# relay_sch.net
KiCad netlist of a schematic drawn in Altium Designer
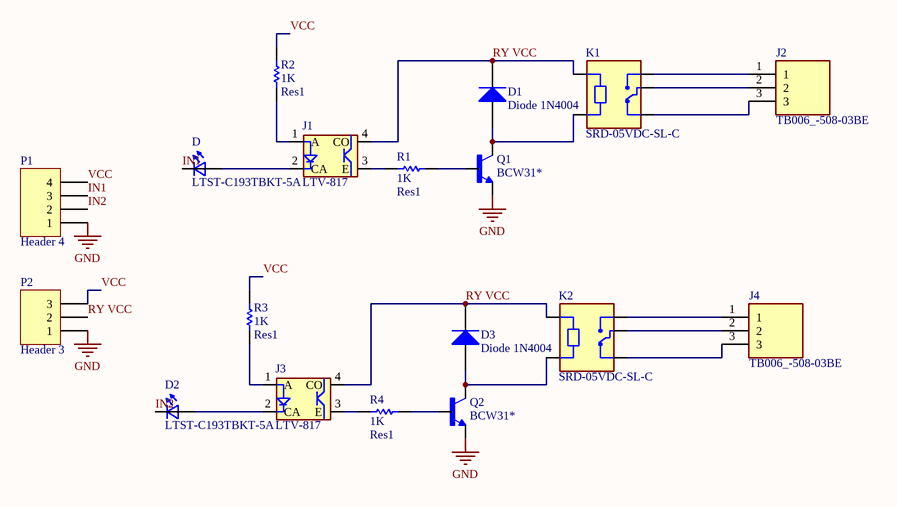
[diagram p0: relay_sch.SchDoc]

(export (version "E")
  (design (tool "Eeschema 10.0.6"))
  (components
    (comp (ref "D")
      (value "LTST-C193TBKT-5A")
      (footprint "0603")
      (description "Blue 470nm LED Indication - Discrete 2.8V 0603 _1608 Metric_")
      (fields (field (name "DIGI-KEY_PART_NUMBER") "160-1827-1-ND") (field (name "MF") "Lite-On Inc."))
      (libsource (lib "SnapEDAsch") (part "LTST-C193TBKT-5A"))
    )
    (comp (ref "D1")
      (value "Diode 1N4004")
      (footprint "DO-41")
      (description "1 Amp General Purpose Rectifier")
      (fields (field (name "PUBLISHER") "Altium Limited"))
      (libsource (lib "Miscellaneous Devices") (part "Diode 1N4004"))
    )
    (comp (ref "D2")
      (value "LTST-C193TBKT-5A")
      (footprint "0603")
      (description "Blue 470nm LED Indication - Discrete 2.8V 0603 _1608 Metric_")
      (fields (field (name "DIGI-KEY_PART_NUMBER") "160-1827-1-ND") (field (name "MF") "Lite-On Inc."))
      (libsource (lib "SnapEDAsch") (part "LTST-C193TBKT-5A"))
    )
    (comp (ref "D3")
      (value "Diode 1N4004")
      (footprint "DO-41")
      (description "1 Amp General Purpose Rectifier")
      (fields (field (name "PUBLISHER") "Altium Limited"))
      (libsource (lib "Miscellaneous Devices") (part "Diode 1N4004"))
    )
    (comp (ref "J1")
      (value "LTV-817")
      (footprint "LTV-817")
      (description "Optoisolator Transistor Output 5000Vrms 1 Channel 4-DIP")
      (fields (field (name "MF") "Lite-On Inc."))
      (libsource (lib "LTV-817") (part "LTV-817"))
    )
    (comp (ref "J2")
      (value "TB006_-508-03BE")
      (footprint "CUI_TB006 -508-03BE")
      (description "2~24 Poles, Screw Type, Horizontal, 5.08 Pitch, 26~14 (AWG), Terminal Block Connector")
      (fields (field (name "MF") "CUI Devices") (field (name "MP") "TB006 -508-03BE"))
      (libsource (lib "TB006_-508-03BE") (part "TB006_-508-03BE"))
    )
    (comp (ref "J3")
      (value "LTV-817")
      (footprint "LTV-817")
      (description "Optoisolator Transistor Output 5000Vrms 1 Channel 4-DIP")
      (fields (field (name "MF") "Lite-On Inc."))
      (libsource (lib "LTV-817") (part "LTV-817"))
    )
    (comp (ref "J4")
      (value "TB006_-508-03BE")
      (footprint "CUI_TB006 -508-03BE")
      (description "2~24 Poles, Screw Type, Horizontal, 5.08 Pitch, 26~14 (AWG), Terminal Block Connector")
      (fields (field (name "MF") "CUI Devices") (field (name "MP") "TB006 -508-03BE"))
      (libsource (lib "TB006_-508-03BE") (part "TB006_-508-03BE"))
    )
    (comp (ref "K1")
      (value "SRD-05VDC-SL-C")
      (footprint "RELAY_SRD-05VDC-SL-C")
      (fields (field (name "MF") "Songle Relay"))
      (libsource (lib "SRD-05VDC-SL-C") (part "SRD-05VDC-SL-C"))
    )
    (comp (ref "K2")
      (value "SRD-05VDC-SL-C")
      (footprint "RELAY_SRD-05VDC-SL-C")
      (fields (field (name "MF") "Songle Relay"))
      (libsource (lib "SRD-05VDC-SL-C") (part "SRD-05VDC-SL-C"))
    )
    (comp (ref "P1")
      (value "Header 4")
      (footprint "HDR1X4")
      (description "Header, 4-Pin")
      (fields (field (name "PUBLISHER") "Altium Limited"))
      (libsource (lib "Miscellaneous Connectors") (part "Header 4"))
    )
    (comp (ref "P2")
      (value "Header 3")
      (footprint "HDR1X3")
      (description "Header, 3-Pin")
      (fields (field (name "PUBLISHER") "Altium Limited"))
      (libsource (lib "Miscellaneous Connectors") (part "Header 3"))
    )
    (comp (ref "Q1")
      (value "BCW31*")
      (footprint "SOT23-BEC")
      (fields (field (name "MF") "Fairchild Semiconductor") (field (name "MP") "BCW31"))
      (libsource (lib "BCW31") (part "BCW31*"))
    )
    (comp (ref "Q2")
      (value "BCW31*")
      (footprint "SOT23-BEC")
      (fields (field (name "MF") "Fairchild Semiconductor") (field (name "MP") "BCW31"))
      (libsource (lib "BCW31") (part "BCW31*"))
    )
    (comp (ref "R1")
      (value "Res1")
      (footprint "AXIAL-0.3")
      (description "Resistor")
      (fields (field (name "ALTIUM_VALUE") "1K") (field (name "PUBLISHER") "Altium Limited"))
      (libsource (lib "Miscellaneous Devices") (part "Res1"))
    )
    (comp (ref "R2")
      (value "Res1")
      (footprint "AXIAL-0.3")
      (description "Resistor")
      (fields (field (name "ALTIUM_VALUE") "1K") (field (name "PUBLISHER") "Altium Limited"))
      (libsource (lib "Miscellaneous Devices") (part "Res1"))
    )
    (comp (ref "R3")
      (value "Res1")
      (footprint "AXIAL-0.3")
      (description "Resistor")
      (fields (field (name "ALTIUM_VALUE") "1K") (field (name "PUBLISHER") "Altium Limited"))
      (libsource (lib "Miscellaneous Devices") (part "Res1"))
    )
    (comp (ref "R4")
      (value "Res1")
      (footprint "AXIAL-0.3")
      (description "Resistor")
      (fields (field (name "ALTIUM_VALUE") "1K") (field (name "PUBLISHER") "Altium Limited"))
      (libsource (lib "Miscellaneous Devices") (part "Res1"))
    )
  )
  (nets
    (net (code "1") (name "/IN1") (class "Default")
      (node (ref "D") (pin "1") (pinfunction "K2_1") (pintype "passive"))
      (node (ref "P1") (pin "3") (pinfunction "3_3") (pintype "passive"))
    )
    (net (code "2") (name "/IN2") (class "Default")
      (node (ref "D2") (pin "1") (pinfunction "K2_1") (pintype "passive"))
      (node (ref "P1") (pin "2") (pinfunction "2_2") (pintype "passive"))
    )
    (net (code "3") (name "/RY VCC") (class "Default")
      (node (ref "D1") (pin "2") (pinfunction "K_2") (pintype "passive"))
      (node (ref "D3") (pin "2") (pinfunction "K_2") (pintype "passive"))
      (node (ref "J1") (pin "4") (pinfunction "CO_4") (pintype "bidirectional"))
      (node (ref "J3") (pin "4") (pinfunction "CO_4") (pintype "bidirectional"))
      (node (ref "K1") (pin "A1") (pinfunction "A1_A1") (pintype "passive"))
      (node (ref "K2") (pin "A1") (pinfunction "A1_A1") (pintype "passive"))
      (node (ref "P2") (pin "2") (pinfunction "2_2") (pintype "passive"))
    )
    (net (code "4") (name "/VCC") (class "Default")
      (node (ref "P1") (pin "4") (pinfunction "4_4") (pintype "passive"))
      (node (ref "P2") (pin "3") (pinfunction "3_3") (pintype "passive"))
      (node (ref "R2") (pin "2") (pinfunction "2_2") (pintype "passive"))
      (node (ref "R3") (pin "2") (pinfunction "2_2") (pintype "passive"))
    )
    (net (code "5") (name "GND") (class "Default")
      (node (ref "P1") (pin "1") (pinfunction "1_1") (pintype "passive"))
      (node (ref "P2") (pin "1") (pinfunction "1_1") (pintype "passive"))
      (node (ref "Q1") (pin "E") (pinfunction "E_E") (pintype "passive"))
      (node (ref "Q2") (pin "E") (pinfunction "E_E") (pintype "passive"))
    )
    (net (code "6") (name "Net-(D-A2)") (class "Default")
      (node (ref "D") (pin "2") (pinfunction "A2_2") (pintype "passive"))
      (node (ref "J1") (pin "2") (pinfunction "CA_2") (pintype "bidirectional"))
    )
    (net (code "7") (name "Net-(D1-A)") (class "Default")
      (node (ref "D1") (pin "1") (pinfunction "A_1") (pintype "passive"))
      (node (ref "K1") (pin "A2") (pinfunction "A2_A2") (pintype "passive"))
      (node (ref "Q1") (pin "C") (pinfunction "C_C") (pintype "passive"))
    )
    (net (code "8") (name "Net-(D2-A2)") (class "Default")
      (node (ref "D2") (pin "2") (pinfunction "A2_2") (pintype "passive"))
      (node (ref "J3") (pin "2") (pinfunction "CA_2") (pintype "bidirectional"))
    )
    (net (code "9") (name "Net-(D3-A)") (class "Default")
      (node (ref "D3") (pin "1") (pinfunction "A_1") (pintype "passive"))
      (node (ref "K2") (pin "A2") (pinfunction "A2_A2") (pintype "passive"))
      (node (ref "Q2") (pin "C") (pinfunction "C_C") (pintype "passive"))
    )
    (net (code "10") (name "Net-(J1-A)") (class "Default")
      (node (ref "J1") (pin "1") (pinfunction "A_1") (pintype "bidirectional"))
      (node (ref "R2") (pin "1") (pinfunction "1_1") (pintype "passive"))
    )
    (net (code "11") (name "Net-(J1-E)") (class "Default")
      (node (ref "J1") (pin "3") (pinfunction "E_3") (pintype "bidirectional"))
      (node (ref "R1") (pin "1") (pinfunction "1_1") (pintype "passive"))
    )
    (net (code "12") (name "Net-(J2-Pad1)") (class "Default")
      (node (ref "J2") (pin "1") (pinfunction "1_1") (pintype "passive"))
      (node (ref "K1") (pin "NO") (pinfunction "NO_NO") (pintype "passive"))
    )
    (net (code "13") (name "Net-(J2-Pad2)") (class "Default")
      (node (ref "J2") (pin "2") (pinfunction "2_2") (pintype "passive"))
      (node (ref "K1") (pin "COM") (pinfunction "COM_COM") (pintype "passive"))
    )
    (net (code "14") (name "Net-(J2-Pad3)") (class "Default")
      (node (ref "J2") (pin "3") (pinfunction "3_3") (pintype "passive"))
      (node (ref "K1") (pin "NC") (pinfunction "NC_NC") (pintype "passive"))
    )
    (net (code "15") (name "Net-(J3-A)") (class "Default")
      (node (ref "J3") (pin "1") (pinfunction "A_1") (pintype "bidirectional"))
      (node (ref "R3") (pin "1") (pinfunction "1_1") (pintype "passive"))
    )
    (net (code "16") (name "Net-(J3-E)") (class "Default")
      (node (ref "J3") (pin "3") (pinfunction "E_3") (pintype "bidirectional"))
      (node (ref "R4") (pin "1") (pinfunction "1_1") (pintype "passive"))
    )
    (net (code "17") (name "Net-(J4-Pad1)") (class "Default")
      (node (ref "J4") (pin "1") (pinfunction "1_1") (pintype "passive"))
      (node (ref "K2") (pin "NO") (pinfunction "NO_NO") (pintype "passive"))
    )
    (net (code "18") (name "Net-(J4-Pad2)") (class "Default")
      (node (ref "J4") (pin "2") (pinfunction "2_2") (pintype "passive"))
      (node (ref "K2") (pin "COM") (pinfunction "COM_COM") (pintype "passive"))
    )
    (net (code "19") (name "Net-(J4-Pad3)") (class "Default")
      (node (ref "J4") (pin "3") (pinfunction "3_3") (pintype "passive"))
      (node (ref "K2") (pin "NC") (pinfunction "NC_NC") (pintype "passive"))
    )
    (net (code "20") (name "Net-(Q1-PadB)") (class "Default")
      (node (ref "Q1") (pin "B") (pinfunction "B_B") (pintype "passive"))
      (node (ref "R1") (pin "2") (pinfunction "2_2") (pintype "passive"))
    )
    (net (code "21") (name "Net-(Q2-PadB)") (class "Default")
      (node (ref "Q2") (pin "B") (pinfunction "B_B") (pintype "passive"))
      (node (ref "R4") (pin "2") (pinfunction "2_2") (pintype "passive"))
    )
  )
)
